# Real_Time_Clock.net
KiCad netlist of a schematic drawn in Altium Designer
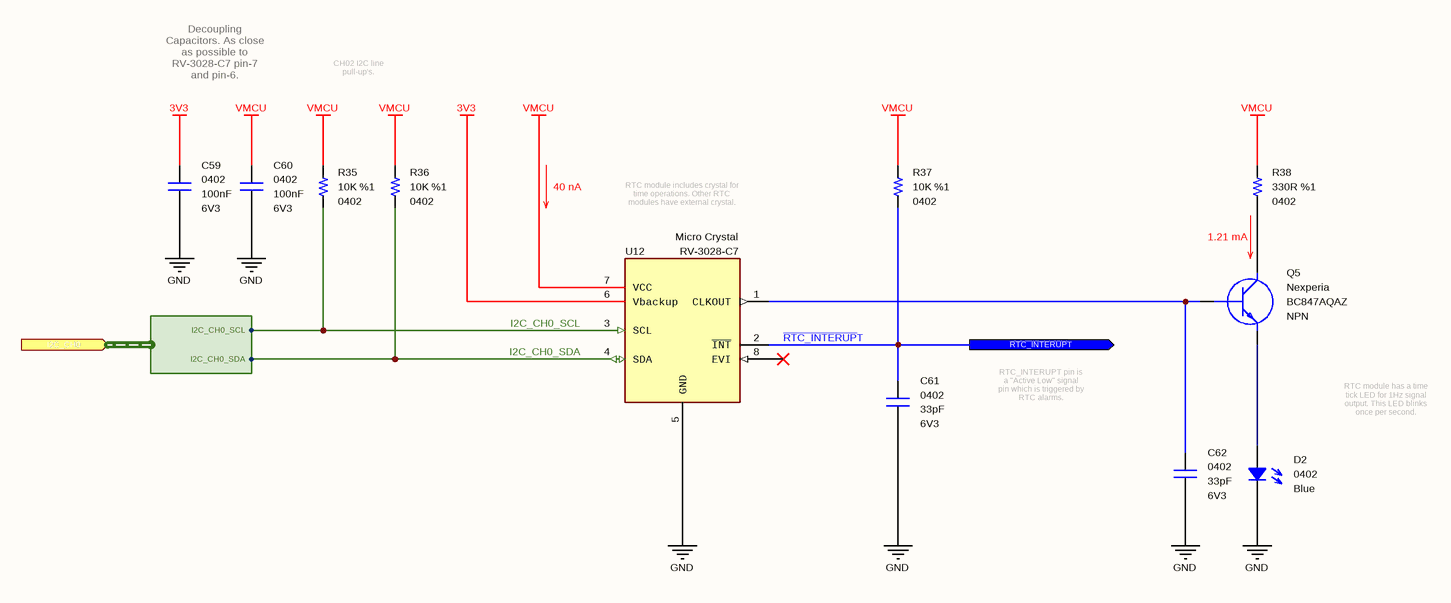
[diagram p0: Real Time Clock.SchDoc]

(export (version "E")
  (design (tool "Eeschema 10.0.6"))
  (components
    (comp (ref "C59")
      (value "100nF")
      (footprint "CAPACITOR_0402")
      (description "Capacitor - 100nF [0402-6V3] (Ceramic)")
      (fields
        (field (name "TOLERANCE") "%10")
        (field (name "CASE") "0402")
        (field (name "VOLTAGE") "6V3")
        (field (name "MANUFACTURER PART NUMBER") "04026D104KAT4A")
      )
      (libsource (lib "Ovoo_Library") (part "Capacitor - 100nF [0402-6V3]"))
    )
    (comp (ref "C60")
      (value "100nF")
      (footprint "CAPACITOR_0402")
      (description "Capacitor - 100nF [0402-6V3] (Ceramic)")
      (fields
        (field (name "TOLERANCE") "%10")
        (field (name "CASE") "0402")
        (field (name "VOLTAGE") "6V3")
        (field (name "MANUFACTURER PART NUMBER") "04026D104KAT4A")
      )
      (libsource (lib "Ovoo_Library") (part "Capacitor - 100nF [0402-6V3]"))
    )
    (comp (ref "C61")
      (value "33pF")
      (footprint "CAPACITOR_0402")
      (description "Capacitor - 33pF [0402] (Ceramic)")
      (fields
        (field (name "CASE") "0402")
        (field (name "TOLERANCE") "10%")
        (field (name "VOLTAGE") "6V3")
        (field (name "MANUFACTURER PART NUMBER") "C0402C330J9RACAUTO")
      )
      (libsource (lib "Ovoo_Library") (part "Capacitor - 33pF [0402-6V3]"))
    )
    (comp (ref "C62")
      (value "33pF")
      (footprint "CAPACITOR_0402")
      (description "Capacitor - 33pF [0402] (Ceramic)")
      (fields
        (field (name "CASE") "0402")
        (field (name "TOLERANCE") "10%")
        (field (name "VOLTAGE") "6V3")
        (field (name "MANUFACTURER PART NUMBER") "C0402C330J9RACAUTO")
      )
      (libsource (lib "Ovoo_Library") (part "Capacitor - 33pF [0402-6V3]"))
    )
    (comp (ref "D2")
      (value "SMD LED (Blue)")
      (footprint "LED_0402")
      (description "Standard LEDs - SMD PICOLEDTM;BLUE LED; 25M @ 5MA")
      (fields
        (field (name "CASE") "0402")
        (field (name "COLOR") "Blue")
        (field (name "MANUFACTURER PART NUMBER") "SMLP13BC8TT86")
        (field (name "MOUSER PART NUMBER") "755-SMLP13BC8TT86")
      )
      (libsource (lib "Ovoo_Library") (part "Diode - LED (0402-Blue)"))
    )
    (comp (ref "Q5")
      (value "BC847AQAZ")
      (footprint "SOT1215")
      (description "Bipolar NPN Transistors")
      (fields
        (field (name "POLARITY") "NPN")
        (field (name "MANUFACTURER NAME") "Nexperia")
        (field (name "MANUFACTURER PART NUMBER") "BC847AQAZ")
      )
      (libsource (lib "Ovoo_Library") (part "Transistor - BC847"))
    )
    (comp (ref "R35")
      (value "10K")
      (footprint "RESISTOR_0402")
      (description "Thick Film Resistors - SMD 1/16 W 10 Kohms 1%")
      (fields
        (field (name "TOLERANCE") "%1")
        (field (name "CASE") "0402")
        (field (name "MANUFACTURER PART NUMBER") "CRCW040210K0FKED")
        (field (name "MOUSER PART NUMBER") "71-CRCW0402-10K-E3")
      )
      (libsource (lib "Ovoo_Library") (part "Resistor - 10K"))
    )
    (comp (ref "R36")
      (value "10K")
      (footprint "RESISTOR_0402")
      (description "Thick Film Resistors - SMD 1/16 W 10 Kohms 1%")
      (fields
        (field (name "TOLERANCE") "%1")
        (field (name "CASE") "0402")
        (field (name "MANUFACTURER PART NUMBER") "CRCW040210K0FKED")
        (field (name "MOUSER PART NUMBER") "71-CRCW0402-10K-E3")
      )
      (libsource (lib "Ovoo_Library") (part "Resistor - 10K"))
    )
    (comp (ref "R37")
      (value "10K")
      (footprint "RESISTOR_0402")
      (description "Thick Film Resistors - SMD 1/16 W 10 Kohms 1%")
      (fields
        (field (name "TOLERANCE") "%1")
        (field (name "CASE") "0402")
        (field (name "MANUFACTURER PART NUMBER") "CRCW040210K0FKED")
        (field (name "MOUSER PART NUMBER") "71-CRCW0402-10K-E3")
      )
      (libsource (lib "Ovoo_Library") (part "Resistor - 10K"))
    )
    (comp (ref "R38")
      (value "330R")
      (footprint "RESISTOR_0402")
      (description "Thick Film Resistors - SMD 1/16 W 330 Ohm 1%")
      (fields
        (field (name "TOLERANCE") "%1")
        (field (name "CASE") "0402")
        (field (name "MANUFACTURER PART NUMBER") "CRCW0402330RFKED")
        (field (name "MOUSER PART NUMBER") "71-CRCW0402-330-E3")
      )
      (libsource (lib "Ovoo_Library") (part "Resistor - 330R"))
    )
    (comp (ref "U12")
      (value "Real Time Clock")
      (footprint "RV-3028-C7")
      (description "Real Time Clock 32.768kHz I2C Time Acc. 1ppm")
      (fields
        (field (name "MOUSER PART NUMBER") "428-203591-MG01")
        (field (name "MANUFACTURER PART NUMBER") "RV-3028-C7")
        (field (name "MANUFACTURER NAME") "Micro Crystal")
      )
      (libsource (lib "Ovoo_Library") (part "IC - RV-3028-C7"))
    )
  )
  (nets
    (net (code "2") (name "/I2C_CH0_SCL") (class "Default")
      (node (ref "R35") (pin "1") (pinfunction "1_1") (pintype "passive"))
      (node (ref "U12") (pin "3") (pinfunction "SCL_3") (pintype "input"))
    )
    (net (code "3") (name "/I2C_CH0_SDA") (class "Default")
      (node (ref "R36") (pin "1") (pinfunction "1_1") (pintype "passive"))
      (node (ref "U12") (pin "4") (pinfunction "SDA_4") (pintype "bidirectional"))
    )
    (net (code "5") (name "/~{RTC_INTERUP}T") (class "Default")
      (node (ref "C61") (pin "1") (pinfunction "1_1") (pintype "passive"))
      (node (ref "R37") (pin "1") (pinfunction "1_1") (pintype "passive"))
      (node (ref "U12") (pin "2") (pinfunction "~{INT}_2") (pintype "open_collector"))
    )
    (net (code "6") (name "3V3") (class "Default")
      (node (ref "C59") (pin "2") (pinfunction "2_2") (pintype "passive"))
      (node (ref "U12") (pin "6") (pinfunction "Vbackup_6") (pintype "power_in"))
    )
    (net (code "7") (name "GND") (class "Default")
      (node (ref "C59") (pin "1") (pinfunction "1_1") (pintype "passive"))
      (node (ref "C60") (pin "1") (pinfunction "1_1") (pintype "passive"))
      (node (ref "C61") (pin "2") (pinfunction "2_2") (pintype "passive"))
      (node (ref "C62") (pin "2") (pinfunction "2_2") (pintype "passive"))
      (node (ref "D2") (pin "1") (pinfunction "1_1") (pintype "passive"))
      (node (ref "U12") (pin "5") (pinfunction "GND_5") (pintype "power_in"))
    )
    (net (code "8") (name "Net-(Q5-B)") (class "Default")
      (node (ref "C62") (pin "1") (pinfunction "1_1") (pintype "passive"))
      (node (ref "Q5") (pin "1") (pinfunction "B_1") (pintype "passive"))
      (node (ref "U12") (pin "1") (pinfunction "CLKOUT_1") (pintype "output"))
    )
    (net (code "9") (name "Net-(Q5-C)") (class "Default")
      (node (ref "Q5") (pin "3") (pinfunction "C_3") (pintype "passive"))
      (node (ref "R38") (pin "1") (pinfunction "1_1") (pintype "passive"))
    )
    (net (code "10") (name "Net-(Q5-E)") (class "Default")
      (node (ref "D2") (pin "2") (pinfunction "2_2") (pintype "passive"))
      (node (ref "Q5") (pin "2") (pinfunction "E_2") (pintype "passive"))
    )
    (net (code "11") (name "VMCU") (class "Default")
      (node (ref "C60") (pin "2") (pinfunction "2_2") (pintype "passive"))
      (node (ref "R35") (pin "2") (pinfunction "2_2") (pintype "passive"))
      (node (ref "R36") (pin "2") (pinfunction "2_2") (pintype "passive"))
      (node (ref "R37") (pin "2") (pinfunction "2_2") (pintype "passive"))
      (node (ref "R38") (pin "2") (pinfunction "2_2") (pintype "passive"))
      (node (ref "U12") (pin "7") (pinfunction "VCC_7") (pintype "power_in"))
    )
    (net (code "12") (name "unconnected-(U12-EVI-Pad8)") (class "Default")
      (node (ref "U12") (pin "8") (pinfunction "EVI_8") (pintype "input+no_connect"))
    )
  )
)
